# MainBoard.net
KiCad netlist of a schematic drawn in EAGLE
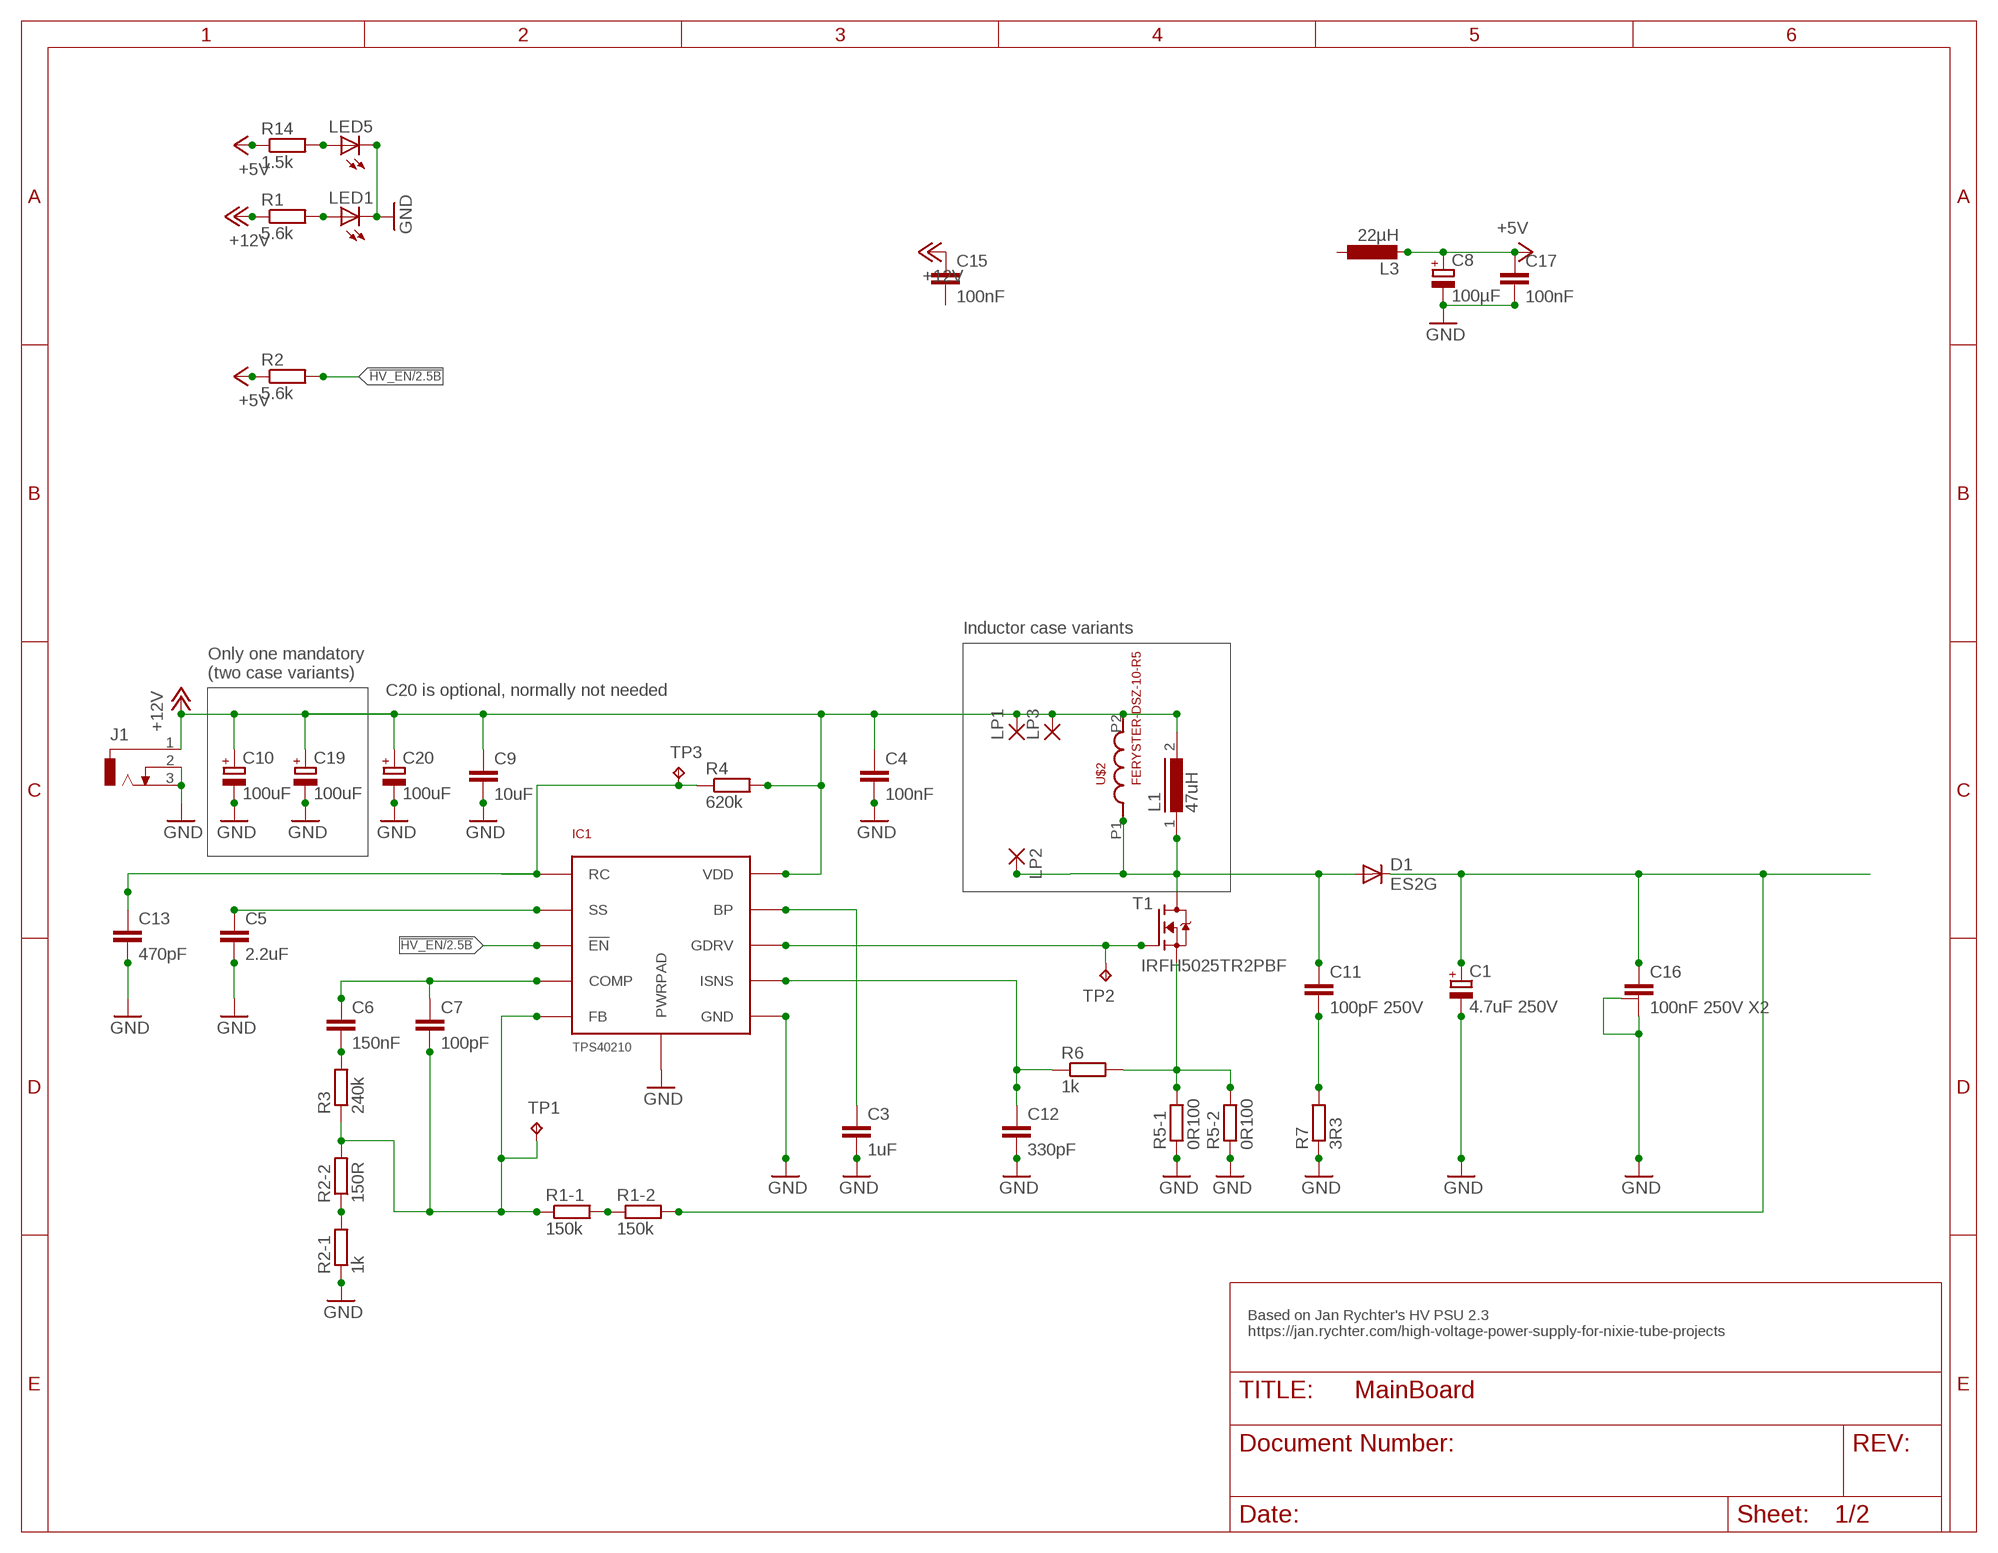
[diagram p0: schematic, sheet 1]
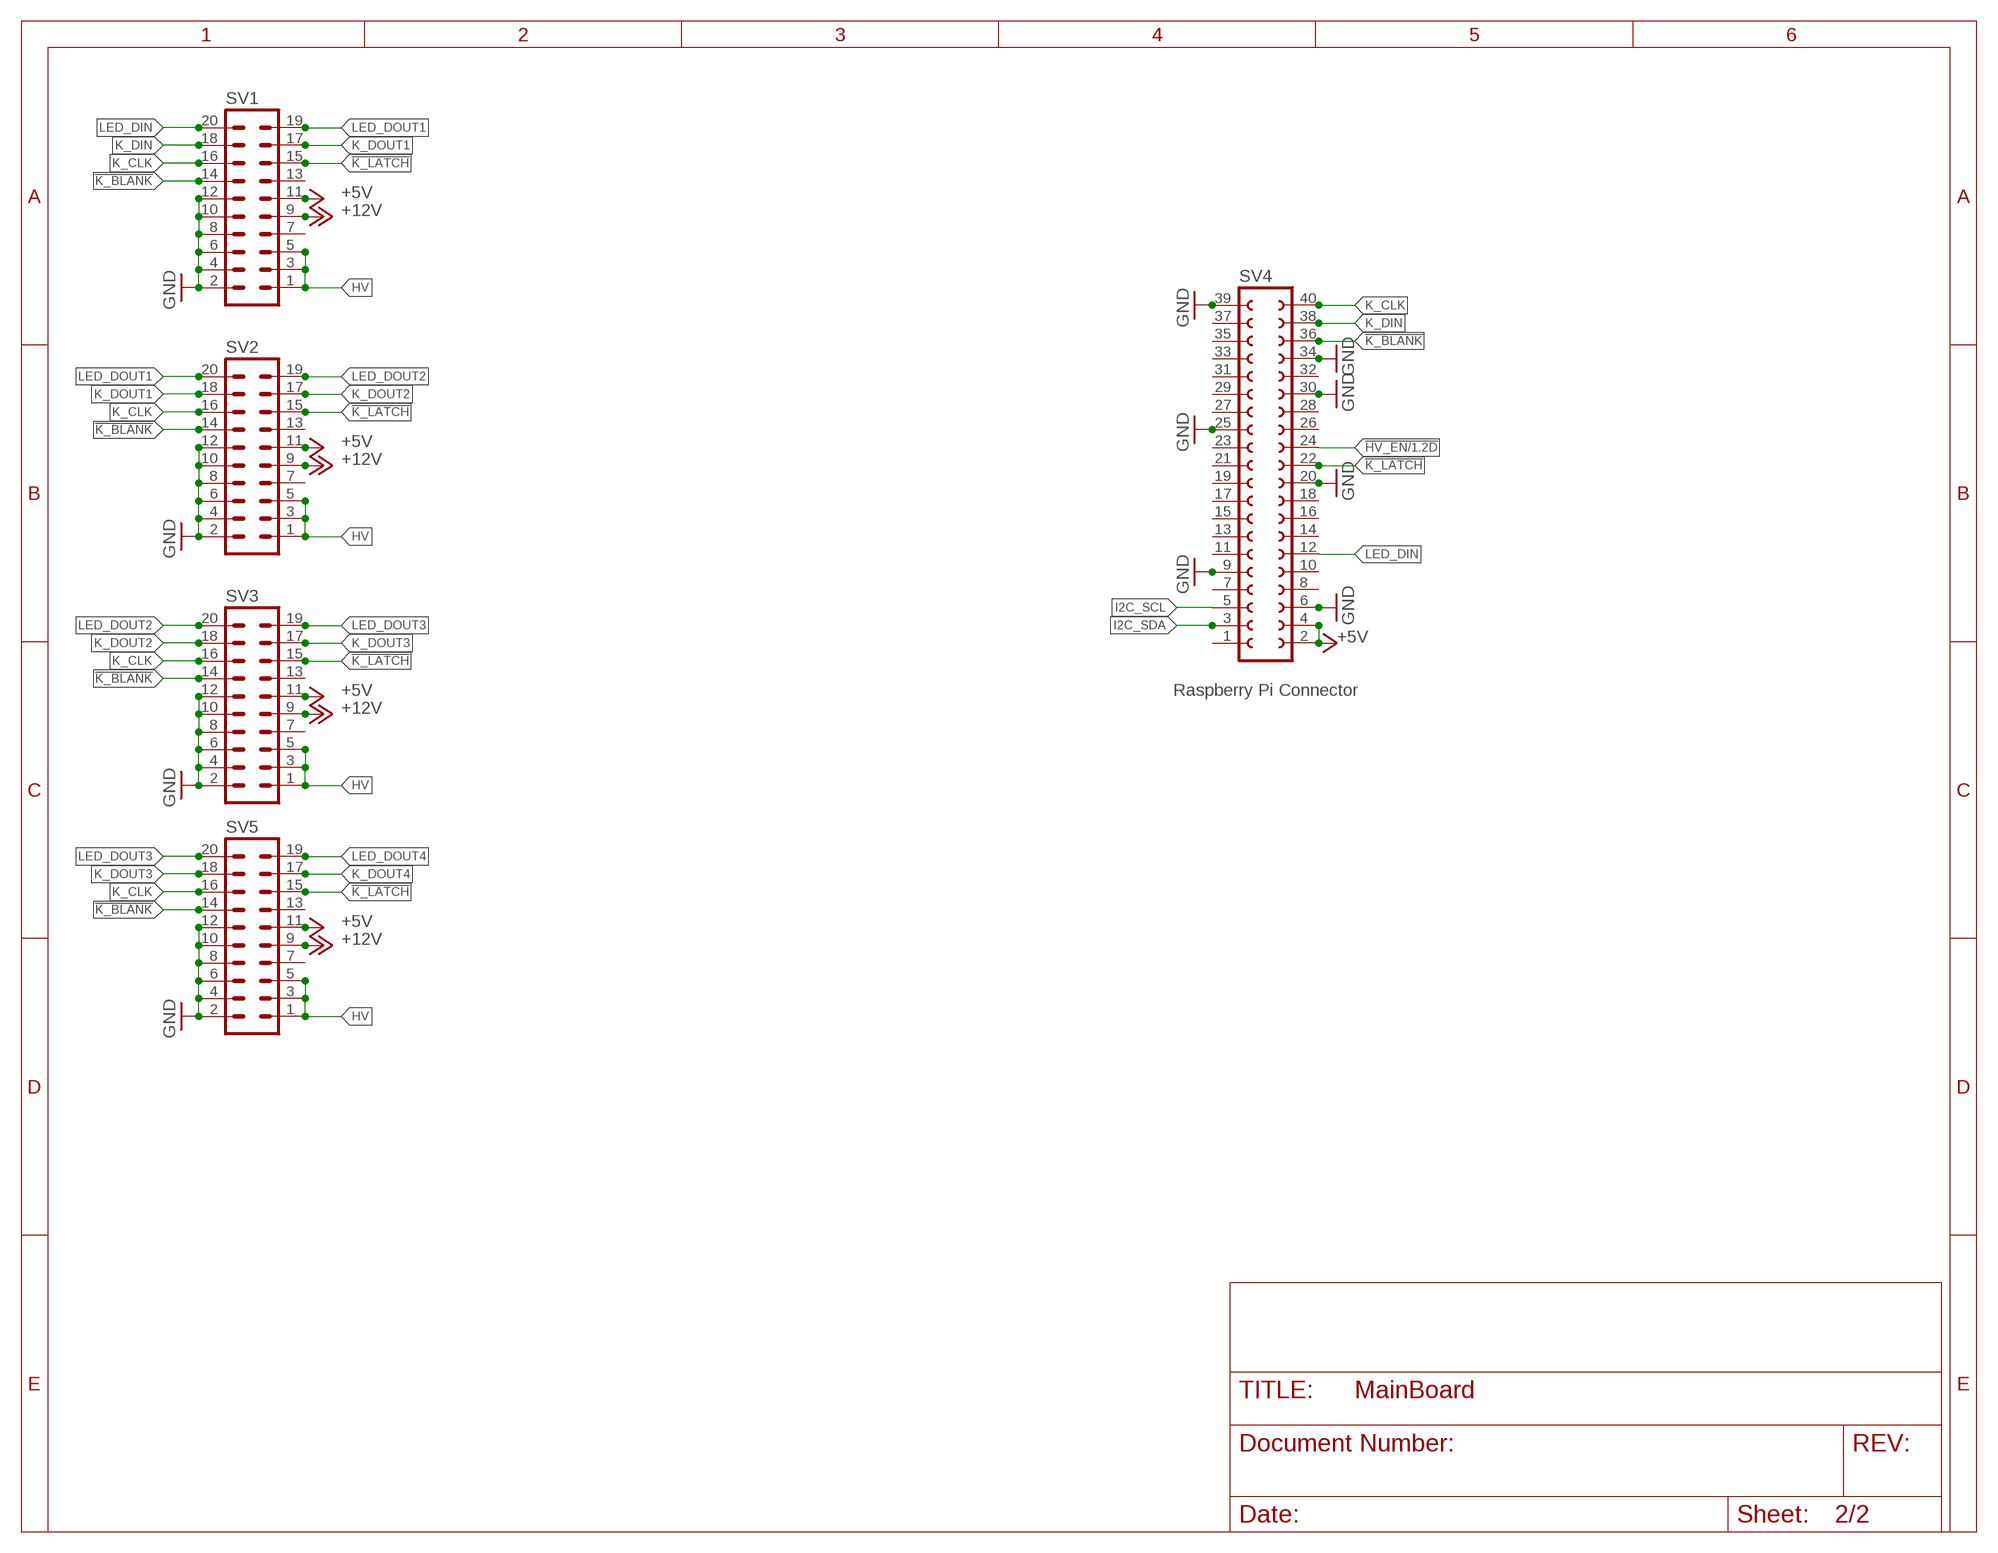
[diagram p1: schematic, sheet 2]

(export (version "E")
  (design (tool "Eeschema 10.0.6"))
  (components
    (comp (ref "SV1")
      (value "MA10-2")
      (footprint "eagle-import:MA10-2")
      (libsource (lib "eagle-import") (part "MA10-2"))
    )
    (comp (ref "SV2")
      (value "MA10-2")
      (footprint "eagle-import:MA10-2")
      (libsource (lib "eagle-import") (part "MA10-2"))
    )
    (comp (ref "SV3")
      (value "MA10-2")
      (footprint "eagle-import:MA10-2")
      (libsource (lib "eagle-import") (part "MA10-2"))
    )
    (comp (ref "SV4")
      (value "FE20-2")
      (footprint "eagle-import:FE20-2")
      (libsource (lib "eagle-import") (part "FE20-2"))
    )
    (comp (ref "SV5")
      (value "MA10-2")
      (footprint "eagle-import:MA10-2")
      (libsource (lib "eagle-import") (part "MA10-2"))
    )
    (comp (ref "C1")
      (value "4.7uF 250V")
      (footprint "eagle-import:E3,5-8")
      (libsource (lib "eagle-import") (part "CPOL-EUE3.5-8"))
    )
    (comp (ref "C3")
      (value "1uF")
      (footprint "eagle-import:C0603")
      (libsource (lib "eagle-import") (part "C-EUC0603"))
    )
    (comp (ref "C4")
      (value "100nF")
      (footprint "eagle-import:C0603")
      (libsource (lib "eagle-import") (part "C-EUC0603"))
    )
    (comp (ref "C5")
      (value "2.2uF")
      (footprint "eagle-import:C1206")
      (libsource (lib "eagle-import") (part "C-EUC1206"))
    )
    (comp (ref "C6")
      (value "150nF")
      (footprint "eagle-import:C0603")
      (libsource (lib "eagle-import") (part "C-EUC0603"))
    )
    (comp (ref "C7")
      (value "100pF")
      (footprint "eagle-import:C0603")
      (libsource (lib "eagle-import") (part "C-EUC0603"))
    )
    (comp (ref "C8")
      (value "100µF")
      (footprint "eagle-import:CT7343")
      (libsource (lib "eagle-import") (part "rcl_334_CPOL-EUCT7343"))
    )
    (comp (ref "C9")
      (value "10uF")
      (footprint "eagle-import:C1206")
      (libsource (lib "eagle-import") (part "C-EUC1206"))
    )
    (comp (ref "C10")
      (value "100uF")
      (footprint "eagle-import:E2,5-6")
      (libsource (lib "eagle-import") (part "CPOL-EUE2.5-6"))
    )
    (comp (ref "C11")
      (value "100pF 250V")
      (footprint "eagle-import:C1812")
      (libsource (lib "eagle-import") (part "C-EUC1812"))
    )
    (comp (ref "C12")
      (value "330pF")
      (footprint "eagle-import:C0603")
      (libsource (lib "eagle-import") (part "C-EUC0603"))
    )
    (comp (ref "C13")
      (value "470pF")
      (footprint "eagle-import:C0603")
      (libsource (lib "eagle-import") (part "C-EUC0603"))
    )
    (comp (ref "C15")
      (value "100nF")
      (footprint "eagle-import:C0805")
      (libsource (lib "eagle-import") (part "rcl_334_C-EUC0805"))
    )
    (comp (ref "C16")
      (value "100nF 250V X2")
      (footprint "eagle-import:C102_152-062X184")
      (libsource (lib "eagle-import") (part "C-EU-3PIN102_152-062X184"))
    )
    (comp (ref "C17")
      (value "100nF")
      (footprint "eagle-import:C0805")
      (libsource (lib "eagle-import") (part "rcl_334_C-EUC0805"))
    )
    (comp (ref "C19")
      (value "100uF")
      (footprint "eagle-import:E3,5-8")
      (libsource (lib "eagle-import") (part "CPOL-EUE3.5-8"))
    )
    (comp (ref "C20")
      (value "100uF")
      (footprint "eagle-import:E2,5-6")
      (libsource (lib "eagle-import") (part "CPOL-EUE2.5-6"))
    )
    (comp (ref "D1")
      (value "ES2G")
      (footprint "eagle-import:DO-214AC")
      (libsource (lib "eagle-import") (part "DIODE-DO-214AC"))
    )
    (comp (ref "IC1")
      (value "TPS40210DGQ")
      (footprint "eagle-import:MSOP10")
      (libsource (lib "eagle-import") (part "TPS40210DGQ"))
    )
    (comp (ref "J1")
      (value "DCJ0303")
      (footprint "eagle-import:DCJ0303")
      (libsource (lib "eagle-import") (part "DCJ0303"))
    )
    (comp (ref "L1")
      (value "47uH")
      (footprint "eagle-import:DR125")
      (libsource (lib "eagle-import") (part "DR125"))
    )
    (comp (ref "L3")
      (value "22µH")
      (footprint "eagle-import:SRR1050A")
      (fields (field (name "MOUSER") "652-SRR1050A-220Y"))
      (libsource (lib "eagle-import") (part "SRR1050A"))
    )
    (comp (ref "LED1")
      (value "LEDCHIPLED_1206")
      (footprint "eagle-import:CHIPLED_1206")
      (libsource (lib "eagle-import") (part "LEDCHIPLED_1206"))
    )
    (comp (ref "LED5")
      (value "LEDCHIPLED_1206")
      (footprint "eagle-import:CHIPLED_1206")
      (libsource (lib "eagle-import") (part "LEDCHIPLED_1206"))
    )
    (comp (ref "LP1")
      (value "3,17/1,3")
      (footprint "eagle-import:3,17_1,3")
      (libsource (lib "eagle-import") (part "3,17/1,3"))
    )
    (comp (ref "LP2")
      (value "3,17/1,3")
      (footprint "eagle-import:3,17_1,3")
      (libsource (lib "eagle-import") (part "3,17/1,3"))
    )
    (comp (ref "LP3")
      (value "3,17/1,3")
      (footprint "eagle-import:3,17_1,3")
      (libsource (lib "eagle-import") (part "3,17/1,3"))
    )
    (comp (ref "R1")
      (value "5.6k")
      (footprint "eagle-import:M0805")
      (libsource (lib "eagle-import") (part "rcl_334_R-EU_M0805"))
    )
    (comp (ref "R1-1")
      (value "150k")
      (footprint "eagle-import:R0805")
      (libsource (lib "eagle-import") (part "R-EU_R0805"))
    )
    (comp (ref "R1-2")
      (value "150k")
      (footprint "eagle-import:R0805")
      (libsource (lib "eagle-import") (part "R-EU_R0805"))
    )
    (comp (ref "R2")
      (value "5.6k")
      (footprint "eagle-import:M0805")
      (libsource (lib "eagle-import") (part "rcl_334_R-EU_M0805"))
    )
    (comp (ref "R2-1")
      (value "1k")
      (footprint "eagle-import:R0603")
      (libsource (lib "eagle-import") (part "R-EU_R0603"))
    )
    (comp (ref "R2-2")
      (value "150R")
      (footprint "eagle-import:R0603")
      (libsource (lib "eagle-import") (part "R-EU_R0603"))
    )
    (comp (ref "R3")
      (value "240k")
      (footprint "eagle-import:R0603")
      (libsource (lib "eagle-import") (part "R-EU_R0603"))
    )
    (comp (ref "R4")
      (value "620k")
      (footprint "eagle-import:R0603")
      (libsource (lib "eagle-import") (part "R-EU_R0603"))
    )
    (comp (ref "R5-1")
      (value "0R100")
      (footprint "eagle-import:R1206")
      (libsource (lib "eagle-import") (part "R-EU_R1206"))
    )
    (comp (ref "R5-2")
      (value "0R100")
      (footprint "eagle-import:R1206")
      (libsource (lib "eagle-import") (part "R-EU_R1206"))
    )
    (comp (ref "R6")
      (value "1k")
      (footprint "eagle-import:R0603")
      (libsource (lib "eagle-import") (part "R-EU_R0603"))
    )
    (comp (ref "R7")
      (value "3R3")
      (footprint "eagle-import:R0805")
      (libsource (lib "eagle-import") (part "R-EU_R0805"))
    )
    (comp (ref "R14")
      (value "1.5k")
      (footprint "eagle-import:M0805")
      (libsource (lib "eagle-import") (part "rcl_334_R-EU_M0805"))
    )
    (comp (ref "T1")
      (value "IRFH5025PBF")
      (footprint "eagle-import:PQFN5X6")
      (libsource (lib "eagle-import") (part "IRFH5025PBF"))
    )
    (comp (ref "TP1")
      (value "TPTP08SQ")
      (footprint "eagle-import:TP08SQ")
      (libsource (lib "eagle-import") (part "TPTP08SQ"))
    )
    (comp (ref "TP2")
      (value "TPTP08SQ")
      (footprint "eagle-import:TP08SQ")
      (libsource (lib "eagle-import") (part "TPTP08SQ"))
    )
    (comp (ref "TP3")
      (value "TPTP08SQ")
      (footprint "eagle-import:TP08SQ")
      (libsource (lib "eagle-import") (part "TPTP08SQ"))
    )
    (comp (ref "U$2")
      (value "FERYSTER-DSZ-10-R5")
      (footprint "eagle-import:DSZ-10-R5")
      (libsource (lib "eagle-import") (part "FERYSTER-DSZ-10-R5"))
    )
  )
  (nets
    (net (code "1") (name "+5V") (class "Default")
      (node (ref "C17") (pin "1") (pinfunction "1_1") (pintype "passive"))
      (node (ref "C8") (pin "+") (pinfunction "+_+") (pintype "passive"))
      (node (ref "L3") (pin "P$2") (pinfunction "2_P$2") (pintype "passive"))
      (node (ref "R14") (pin "1") (pinfunction "1_1") (pintype "passive"))
      (node (ref "R2") (pin "1") (pinfunction "1_1") (pintype "passive"))
      (node (ref "SV1") (pin "11") (pinfunction "11_11") (pintype "passive"))
      (node (ref "SV2") (pin "11") (pinfunction "11_11") (pintype "passive"))
      (node (ref "SV3") (pin "11") (pinfunction "11_11") (pintype "passive"))
      (node (ref "SV4") (pin "2") (pinfunction "2_2") (pintype "passive"))
      (node (ref "SV4") (pin "4") (pinfunction "4_4") (pintype "passive"))
      (node (ref "SV5") (pin "11") (pinfunction "11_11") (pintype "passive"))
    )
    (net (code "2") (name "+12V") (class "Default")
      (node (ref "C10") (pin "+") (pinfunction "+_+") (pintype "passive"))
      (node (ref "C15") (pin "1") (pinfunction "1_1") (pintype "passive"))
      (node (ref "C19") (pin "+") (pinfunction "+_+") (pintype "passive"))
      (node (ref "C20") (pin "+") (pinfunction "+_+") (pintype "passive"))
      (node (ref "C4") (pin "1") (pinfunction "1_1") (pintype "passive"))
      (node (ref "C9") (pin "1") (pinfunction "1_1") (pintype "passive"))
      (node (ref "IC1") (pin "P$10") (pinfunction "VDD_P$10") (pintype "power_in"))
      (node (ref "J1") (pin "1") (pinfunction "1_1") (pintype "passive"))
      (node (ref "L1") (pin "2") (pinfunction "2_2") (pintype "passive"))
      (node (ref "LP1") (pin "1") (pinfunction "P_1") (pintype "passive"))
      (node (ref "LP3") (pin "1") (pinfunction "P_1") (pintype "passive"))
      (node (ref "R1") (pin "1") (pinfunction "1_1") (pintype "passive"))
      (node (ref "R4") (pin "2") (pinfunction "2_2") (pintype "passive"))
      (node (ref "SV1") (pin "9") (pinfunction "9_9") (pintype "passive"))
      (node (ref "SV2") (pin "9") (pinfunction "9_9") (pintype "passive"))
      (node (ref "SV3") (pin "9") (pinfunction "9_9") (pintype "passive"))
      (node (ref "SV5") (pin "9") (pinfunction "9_9") (pintype "passive"))
      (node (ref "U$2") (pin "P2") (pinfunction "P2_P2") (pintype "passive"))
    )
    (net (code "3") (name "GND") (class "Default")
      (node (ref "C1") (pin "-") (pinfunction "-_-") (pintype "passive"))
      (node (ref "C10") (pin "-") (pinfunction "-_-") (pintype "passive"))
      (node (ref "C12") (pin "2") (pinfunction "2_2") (pintype "passive"))
      (node (ref "C13") (pin "2") (pinfunction "2_2") (pintype "passive"))
      (node (ref "C16") (pin "2") (pinfunction "2_2") (pintype "passive"))
      (node (ref "C16") (pin "3") (pinfunction "3_3") (pintype "passive"))
      (node (ref "C17") (pin "2") (pinfunction "2_2") (pintype "passive"))
      (node (ref "C19") (pin "-") (pinfunction "-_-") (pintype "passive"))
      (node (ref "C20") (pin "-") (pinfunction "-_-") (pintype "passive"))
      (node (ref "C3") (pin "2") (pinfunction "2_2") (pintype "passive"))
      (node (ref "C4") (pin "2") (pinfunction "2_2") (pintype "passive"))
      (node (ref "C5") (pin "2") (pinfunction "2_2") (pintype "passive"))
      (node (ref "C8") (pin "-") (pinfunction "-_-") (pintype "passive"))
      (node (ref "C9") (pin "2") (pinfunction "2_2") (pintype "passive"))
      (node (ref "IC1") (pin "P$6") (pinfunction "GND_P$6") (pintype "power_in"))
      (node (ref "IC1") (pin "PWRPAD") (pinfunction "PWRPAD_PWRPAD") (pintype "bidirectional"))
      (node (ref "J1") (pin "2") (pinfunction "2_2") (pintype "passive"))
      (node (ref "J1") (pin "3") (pinfunction "3_3") (pintype "passive"))
      (node (ref "LED1") (pin "C") (pinfunction "C_C") (pintype "passive"))
      (node (ref "LED5") (pin "C") (pinfunction "C_C") (pintype "passive"))
      (node (ref "R2-1") (pin "1") (pinfunction "1_1") (pintype "passive"))
      (node (ref "R5-1") (pin "1") (pinfunction "1_1") (pintype "passive"))
      (node (ref "R5-2") (pin "1") (pinfunction "1_1") (pintype "passive"))
      (node (ref "R7") (pin "1") (pinfunction "1_1") (pintype "passive"))
      (node (ref "SV1") (pin "10") (pinfunction "10_10") (pintype "passive"))
      (node (ref "SV1") (pin "12") (pinfunction "12_12") (pintype "passive"))
      (node (ref "SV1") (pin "2") (pinfunction "2_2") (pintype "passive"))
      (node (ref "SV1") (pin "4") (pinfunction "4_4") (pintype "passive"))
      (node (ref "SV1") (pin "6") (pinfunction "6_6") (pintype "passive"))
      (node (ref "SV1") (pin "8") (pinfunction "8_8") (pintype "passive"))
      (node (ref "SV2") (pin "10") (pinfunction "10_10") (pintype "passive"))
      (node (ref "SV2") (pin "12") (pinfunction "12_12") (pintype "passive"))
      (node (ref "SV2") (pin "2") (pinfunction "2_2") (pintype "passive"))
      (node (ref "SV2") (pin "4") (pinfunction "4_4") (pintype "passive"))
      (node (ref "SV2") (pin "6") (pinfunction "6_6") (pintype "passive"))
      (node (ref "SV2") (pin "8") (pinfunction "8_8") (pintype "passive"))
      (node (ref "SV3") (pin "10") (pinfunction "10_10") (pintype "passive"))
      (node (ref "SV3") (pin "12") (pinfunction "12_12") (pintype "passive"))
      (node (ref "SV3") (pin "2") (pinfunction "2_2") (pintype "passive"))
      (node (ref "SV3") (pin "4") (pinfunction "4_4") (pintype "passive"))
      (node (ref "SV3") (pin "6") (pinfunction "6_6") (pintype "passive"))
      (node (ref "SV3") (pin "8") (pinfunction "8_8") (pintype "passive"))
      (node (ref "SV4") (pin "20") (pinfunction "20_20") (pintype "passive"))
      (node (ref "SV4") (pin "25") (pinfunction "25_25") (pintype "passive"))
      (node (ref "SV4") (pin "30") (pinfunction "30_30") (pintype "passive"))
      (node (ref "SV4") (pin "34") (pinfunction "34_34") (pintype "passive"))
      (node (ref "SV4") (pin "39") (pinfunction "39_39") (pintype "passive"))
      (node (ref "SV4") (pin "6") (pinfunction "6_6") (pintype "passive"))
      (node (ref "SV4") (pin "9") (pinfunction "9_9") (pintype "passive"))
      (node (ref "SV5") (pin "10") (pinfunction "10_10") (pintype "passive"))
      (node (ref "SV5") (pin "12") (pinfunction "12_12") (pintype "passive"))
      (node (ref "SV5") (pin "2") (pinfunction "2_2") (pintype "passive"))
      (node (ref "SV5") (pin "4") (pinfunction "4_4") (pintype "passive"))
      (node (ref "SV5") (pin "6") (pinfunction "6_6") (pintype "passive"))
      (node (ref "SV5") (pin "8") (pinfunction "8_8") (pintype "passive"))
    )
    (net (code "4") (name "HV") (class "Default")
      (node (ref "C1") (pin "+") (pinfunction "+_+") (pintype "passive"))
      (node (ref "C16") (pin "1") (pinfunction "1_1") (pintype "passive"))
      (node (ref "D1") (pin "C") (pinfunction "C_C") (pintype "passive"))
      (node (ref "R1-2") (pin "2") (pinfunction "2_2") (pintype "passive"))
      (node (ref "SV1") (pin "1") (pinfunction "1_1") (pintype "passive"))
      (node (ref "SV1") (pin "3") (pinfunction "3_3") (pintype "passive"))
      (node (ref "SV1") (pin "5") (pinfunction "5_5") (pintype "passive"))
      (node (ref "SV2") (pin "1") (pinfunction "1_1") (pintype "passive"))
      (node (ref "SV2") (pin "3") (pinfunction "3_3") (pintype "passive"))
      (node (ref "SV2") (pin "5") (pinfunction "5_5") (pintype "passive"))
      (node (ref "SV3") (pin "1") (pinfunction "1_1") (pintype "passive"))
      (node (ref "SV3") (pin "3") (pinfunction "3_3") (pintype "passive"))
      (node (ref "SV3") (pin "5") (pinfunction "5_5") (pintype "passive"))
      (node (ref "SV5") (pin "1") (pinfunction "1_1") (pintype "passive"))
      (node (ref "SV5") (pin "3") (pinfunction "3_3") (pintype "passive"))
      (node (ref "SV5") (pin "5") (pinfunction "5_5") (pintype "passive"))
    )
    (net (code "5") (name "I2C_SCL") (class "Default")
      (node (ref "SV4") (pin "5") (pinfunction "5_5") (pintype "passive"))
    )
    (net (code "6") (name "I2C_SDA") (class "Default")
      (node (ref "SV4") (pin "3") (pinfunction "3_3") (pintype "passive"))
    )
    (net (code "7") (name "K_CLK") (class "Default")
      (node (ref "SV1") (pin "16") (pinfunction "16_16") (pintype "passive"))
      (node (ref "SV2") (pin "16") (pinfunction "16_16") (pintype "passive"))
      (node (ref "SV3") (pin "16") (pinfunction "16_16") (pintype "passive"))
      (node (ref "SV4") (pin "40") (pinfunction "40_40") (pintype "passive"))
      (node (ref "SV5") (pin "16") (pinfunction "16_16") (pintype "passive"))
    )
    (net (code "8") (name "K_DIN") (class "Default")
      (node (ref "SV1") (pin "18") (pinfunction "18_18") (pintype "passive"))
      (node (ref "SV4") (pin "38") (pinfunction "38_38") (pintype "passive"))
    )
    (net (code "9") (name "K_DOUT1") (class "Default")
      (node (ref "SV1") (pin "17") (pinfunction "17_17") (pintype "passive"))
      (node (ref "SV2") (pin "18") (pinfunction "18_18") (pintype "passive"))
    )
    (net (code "10") (name "K_DOUT2") (class "Default")
      (node (ref "SV2") (pin "17") (pinfunction "17_17") (pintype "passive"))
      (node (ref "SV3") (pin "18") (pinfunction "18_18") (pintype "passive"))
    )
    (net (code "11") (name "K_DOUT3") (class "Default")
      (node (ref "SV3") (pin "17") (pinfunction "17_17") (pintype "passive"))
      (node (ref "SV5") (pin "18") (pinfunction "18_18") (pintype "passive"))
    )
    (net (code "12") (name "K_DOUT4") (class "Default")
      (node (ref "SV5") (pin "17") (pinfunction "17_17") (pintype "passive"))
    )
    (net (code "13") (name "LED_DIN") (class "Default")
      (node (ref "SV1") (pin "20") (pinfunction "20_20") (pintype "passive"))
      (node (ref "SV4") (pin "12") (pinfunction "12_12") (pintype "passive"))
    )
    (net (code "14") (name "LED_DOUT1") (class "Default")
      (node (ref "SV1") (pin "19") (pinfunction "19_19") (pintype "passive"))
      (node (ref "SV2") (pin "20") (pinfunction "20_20") (pintype "passive"))
    )
    (net (code "15") (name "LED_DOUT2") (class "Default")
      (node (ref "SV2") (pin "19") (pinfunction "19_19") (pintype "passive"))
      (node (ref "SV3") (pin "20") (pinfunction "20_20") (pintype "passive"))
    )
    (net (code "16") (name "LED_DOUT3") (class "Default")
      (node (ref "SV3") (pin "19") (pinfunction "19_19") (pintype "passive"))
      (node (ref "SV5") (pin "20") (pinfunction "20_20") (pintype "passive"))
    )
    (net (code "17") (name "LED_DOUT4") (class "Default")
      (node (ref "SV5") (pin "19") (pinfunction "19_19") (pintype "passive"))
    )
    (net (code "18") (name "Net-(C6-Pad2)") (class "Default")
      (node (ref "C6") (pin "2") (pinfunction "2_2") (pintype "passive"))
      (node (ref "R3") (pin "2") (pinfunction "2_2") (pintype "passive"))
    )
    (net (code "19") (name "Net-(C11-Pad2)") (class "Default")
      (node (ref "C11") (pin "2") (pinfunction "2_2") (pintype "passive"))
      (node (ref "R7") (pin "2") (pinfunction "2_2") (pintype "passive"))
    )
    (net (code "20") (name "Net-(IC1-BP)") (class "Default")
      (node (ref "C3") (pin "1") (pinfunction "1_1") (pintype "passive"))
      (node (ref "IC1") (pin "P$9") (pinfunction "BP_P$9") (pintype "bidirectional"))
    )
    (net (code "21") (name "Net-(IC1-COMP)") (class "Default")
      (node (ref "C6") (pin "1") (pinfunction "1_1") (pintype "passive"))
      (node (ref "C7") (pin "1") (pinfunction "1_1") (pintype "passive"))
      (node (ref "IC1") (pin "P$4") (pinfunction "COMP_P$4") (pintype "bidirectional"))
    )
    (net (code "22") (name "Net-(IC1-FB)") (class "Default")
      (node (ref "C7") (pin "2") (pinfunction "2_2") (pintype "passive"))
      (node (ref "IC1") (pin "P$5") (pinfunction "FB_P$5") (pintype "bidirectional"))
      (node (ref "R1-1") (pin "1") (pinfunction "1_1") (pintype "passive"))
      (node (ref "R2-2") (pin "2") (pinfunction "2_2") (pintype "passive"))
      (node (ref "R3") (pin "1") (pinfunction "1_1") (pintype "passive"))
      (node (ref "TP1") (pin "TP") (pinfunction "TP_TP") (pintype "input"))
    )
    (net (code "23") (name "Net-(IC1-GDRV)") (class "Default")
      (node (ref "IC1") (pin "P$8") (pinfunction "GDRV_P$8") (pintype "bidirectional"))
      (node (ref "T1") (pin "G") (pinfunction "G_G") (pintype "passive"))
      (node (ref "TP2") (pin "TP") (pinfunction "TP_TP") (pintype "input"))
    )
    (net (code "24") (name "Net-(IC1-ISNS)") (class "Default")
      (node (ref "C12") (pin "1") (pinfunction "1_1") (pintype "passive"))
      (node (ref "IC1") (pin "P$7") (pinfunction "ISNS_P$7") (pintype "bidirectional"))
      (node (ref "R6") (pin "1") (pinfunction "1_1") (pintype "passive"))
    )
    (net (code "25") (name "Net-(IC1-RC)") (class "Default")
      (node (ref "C13") (pin "1") (pinfunction "1_1") (pintype "passive"))
      (node (ref "IC1") (pin "P$1") (pinfunction "RC_P$1") (pintype "bidirectional"))
      (node (ref "R4") (pin "1") (pinfunction "1_1") (pintype "passive"))
      (node (ref "TP3") (pin "TP") (pinfunction "TP_TP") (pintype "input"))
    )
    (net (code "26") (name "Net-(IC1-SS)") (class "Default")
      (node (ref "C5") (pin "1") (pinfunction "1_1") (pintype "passive"))
      (node (ref "IC1") (pin "P$2") (pinfunction "SS_P$2") (pintype "bidirectional"))
    )
    (net (code "27") (name "Net-(LED1-PadA)") (class "Default")
      (node (ref "LED1") (pin "A") (pinfunction "A_A") (pintype "passive"))
      (node (ref "R1") (pin "2") (pinfunction "2_2") (pintype "passive"))
    )
    (net (code "28") (name "Net-(LED5-PadA)") (class "Default")
      (node (ref "LED5") (pin "A") (pinfunction "A_A") (pintype "passive"))
      (node (ref "R14") (pin "2") (pinfunction "2_2") (pintype "passive"))
    )
    (net (code "29") (name "Net-(LP2-P)") (class "Default")
      (node (ref "C11") (pin "1") (pinfunction "1_1") (pintype "passive"))
      (node (ref "D1") (pin "A") (pinfunction "A_A") (pintype "passive"))
      (node (ref "L1") (pin "1") (pinfunction "1_1") (pintype "passive"))
      (node (ref "LP2") (pin "1") (pinfunction "P_1") (pintype "passive"))
      (node (ref "T1") (pin "D1") (pinfunction "D_D1") (pintype "passive"))
      (node (ref "T1") (pin "D2") (pinfunction "D_D2") (pintype "passive"))
      (node (ref "T1") (pin "D3") (pinfunction "D_D3") (pintype "passive"))
      (node (ref "T1") (pin "D4") (pinfunction "D_D4") (pintype "passive"))
      (node (ref "T1") (pin "D5") (pinfunction "D_D5") (pintype "passive"))
      (node (ref "U$2") (pin "P1") (pinfunction "P1_P1") (pintype "passive"))
    )
    (net (code "30") (name "Net-(R1-1-Pad2)") (class "Default")
      (node (ref "R1-1") (pin "2") (pinfunction "2_2") (pintype "passive"))
      (node (ref "R1-2") (pin "1") (pinfunction "1_1") (pintype "passive"))
    )
    (net (code "31") (name "Net-(R2-1-Pad2)") (class "Default")
      (node (ref "R2-1") (pin "2") (pinfunction "2_2") (pintype "passive"))
      (node (ref "R2-2") (pin "1") (pinfunction "1_1") (pintype "passive"))
    )
    (net (code "32") (name "Net-(R5-1-Pad2)") (class "Default")
      (node (ref "R5-1") (pin "2") (pinfunction "2_2") (pintype "passive"))
      (node (ref "R5-2") (pin "2") (pinfunction "2_2") (pintype "passive"))
      (node (ref "R6") (pin "2") (pinfunction "2_2") (pintype "passive"))
      (node (ref "T1") (pin "S1") (pinfunction "S_S1") (pintype "passive"))
      (node (ref "T1") (pin "S2") (pinfunction "S_S2") (pintype "passive"))
      (node (ref "T1") (pin "S3") (pinfunction "S_S3") (pintype "passive"))
      (node (ref "T1") (pin "S4") (pinfunction "S_S4") (pintype "passive"))
    )
    (net (code "33") (name "unconnected-(C15-Pad2)") (class "Default")
      (node (ref "C15") (pin "2") (pinfunction "2_2") (pintype "passive"))
    )
    (net (code "34") (name "unconnected-(L3-1-PadP$1)") (class "Default")
      (node (ref "L3") (pin "P$1") (pinfunction "1_P$1") (pintype "passive"))
    )
    (net (code "35") (name "unconnected-(SV1-Pad7)") (class "Default")
      (node (ref "SV1") (pin "7") (pinfunction "7_7") (pintype "passive"))
    )
    (net (code "36") (name "unconnected-(SV1-Pad13)") (class "Default")
      (node (ref "SV1") (pin "13") (pinfunction "13_13") (pintype "passive"))
    )
    (net (code "37") (name "unconnected-(SV2-Pad7)") (class "Default")
      (node (ref "SV2") (pin "7") (pinfunction "7_7") (pintype "passive"))
    )
    (net (code "38") (name "unconnected-(SV2-Pad13)") (class "Default")
      (node (ref "SV2") (pin "13") (pinfunction "13_13") (pintype "passive"))
    )
    (net (code "39") (name "unconnected-(SV3-Pad7)") (class "Default")
      (node (ref "SV3") (pin "7") (pinfunction "7_7") (pintype "passive"))
    )
    (net (code "40") (name "unconnected-(SV3-Pad13)") (class "Default")
      (node (ref "SV3") (pin "13") (pinfunction "13_13") (pintype "passive"))
    )
    (net (code "41") (name "unconnected-(SV4-Pad1)") (class "Default")
      (node (ref "SV4") (pin "1") (pinfunction "1_1") (pintype "passive"))
    )
    (net (code "42") (name "unconnected-(SV4-Pad7)") (class "Default")
      (node (ref "SV4") (pin "7") (pinfunction "7_7") (pintype "passive"))
    )
    (net (code "43") (name "unconnected-(SV4-Pad8)") (class "Default")
      (node (ref "SV4") (pin "8") (pinfunction "8_8") (pintype "passive"))
    )
    (net (code "44") (name "unconnected-(SV4-Pad10)") (class "Default")
      (node (ref "SV4") (pin "10") (pinfunction "10_10") (pintype "passive"))
    )
    (net (code "45") (name "unconnected-(SV4-Pad11)") (class "Default")
      (node (ref "SV4") (pin "11") (pinfunction "11_11") (pintype "passive"))
    )
    (net (code "46") (name "unconnected-(SV4-Pad13)") (class "Default")
      (node (ref "SV4") (pin "13") (pinfunction "13_13") (pintype "passive"))
    )
    (net (code "47") (name "unconnected-(SV4-Pad14)") (class "Default")
      (node (ref "SV4") (pin "14") (pinfunction "14_14") (pintype "passive"))
    )
    (net (code "48") (name "unconnected-(SV4-Pad15)") (class "Default")
      (node (ref "SV4") (pin "15") (pinfunction "15_15") (pintype "passive"))
    )
    (net (code "49") (name "unconnected-(SV4-Pad16)") (class "Default")
      (node (ref "SV4") (pin "16") (pinfunction "16_16") (pintype "passive"))
    )
    (net (code "50") (name "unconnected-(SV4-Pad17)") (class "Default")
      (node (ref "SV4") (pin "17") (pinfunction "17_17") (pintype "passive"))
    )
    (net (code "51") (name "unconnected-(SV4-Pad18)") (class "Default")
      (node (ref "SV4") (pin "18") (pinfunction "18_18") (pintype "passive"))
    )
    (net (code "52") (name "unconnected-(SV4-Pad19)") (class "Default")
      (node (ref "SV4") (pin "19") (pinfunction "19_19") (pintype "passive"))
    )
    (net (code "53") (name "unconnected-(SV4-Pad21)") (class "Default")
      (node (ref "SV4") (pin "21") (pinfunction "21_21") (pintype "passive"))
    )
    (net (code "54") (name "unconnected-(SV4-Pad23)") (class "Default")
      (node (ref "SV4") (pin "23") (pinfunction "23_23") (pintype "passive"))
    )
    (net (code "55") (name "unconnected-(SV4-Pad26)") (class "Default")
      (node (ref "SV4") (pin "26") (pinfunction "26_26") (pintype "passive"))
    )
    (net (code "56") (name "unconnected-(SV4-Pad27)") (class "Default")
      (node (ref "SV4") (pin "27") (pinfunction "27_27") (pintype "passive"))
    )
    (net (code "57") (name "unconnected-(SV4-Pad28)") (class "Default")
      (node (ref "SV4") (pin "28") (pinfunction "28_28") (pintype "passive"))
    )
    (net (code "58") (name "unconnected-(SV4-Pad29)") (class "Default")
      (node (ref "SV4") (pin "29") (pinfunction "29_29") (pintype "passive"))
    )
    (net (code "59") (name "unconnected-(SV4-Pad31)") (class "Default")
      (node (ref "SV4") (pin "31") (pinfunction "31_31") (pintype "passive"))
    )
    (net (code "60") (name "unconnected-(SV4-Pad32)") (class "Default")
      (node (ref "SV4") (pin "32") (pinfunction "32_32") (pintype "passive"))
    )
    (net (code "61") (name "unconnected-(SV4-Pad33)") (class "Default")
      (node (ref "SV4") (pin "33") (pinfunction "33_33") (pintype "passive"))
    )
    (net (code "62") (name "unconnected-(SV4-Pad35)") (class "Default")
      (node (ref "SV4") (pin "35") (pinfunction "35_35") (pintype "passive"))
    )
    (net (code "63") (name "unconnected-(SV4-Pad37)") (class "Default")
      (node (ref "SV4") (pin "37") (pinfunction "37_37") (pintype "passive"))
    )
    (net (code "64") (name "unconnected-(SV5-Pad7)") (class "Default")
      (node (ref "SV5") (pin "7") (pinfunction "7_7") (pintype "passive"))
    )
    (net (code "65") (name "unconnected-(SV5-Pad13)") (class "Default")
      (node (ref "SV5") (pin "13") (pinfunction "13_13") (pintype "passive"))
    )
    (net (code "66") (name "~{HV_EN}") (class "Default")
      (node (ref "IC1") (pin "P$3") (pinfunction "~{EN}_P$3") (pintype "bidirectional"))
      (node (ref "R2") (pin "2") (pinfunction "2_2") (pintype "passive"))
      (node (ref "SV4") (pin "24") (pinfunction "24_24") (pintype "passive"))
    )
    (net (code "67") (name "~{K_BLANK}") (class "Default")
      (node (ref "SV1") (pin "14") (pinfunction "14_14") (pintype "passive"))
      (node (ref "SV2") (pin "14") (pinfunction "14_14") (pintype "passive"))
      (node (ref "SV3") (pin "14") (pinfunction "14_14") (pintype "passive"))
      (node (ref "SV4") (pin "36") (pinfunction "36_36") (pintype "passive"))
      (node (ref "SV5") (pin "14") (pinfunction "14_14") (pintype "passive"))
    )
    (net (code "68") (name "~{K_LATCH}") (class "Default")
      (node (ref "SV1") (pin "15") (pinfunction "15_15") (pintype "passive"))
      (node (ref "SV2") (pin "15") (pinfunction "15_15") (pintype "passive"))
      (node (ref "SV3") (pin "15") (pinfunction "15_15") (pintype "passive"))
      (node (ref "SV4") (pin "22") (pinfunction "22_22") (pintype "passive"))
      (node (ref "SV5") (pin "15") (pinfunction "15_15") (pintype "passive"))
    )
  )
)
